# lvc.net
KiCad netlist of a schematic drawn in EAGLE
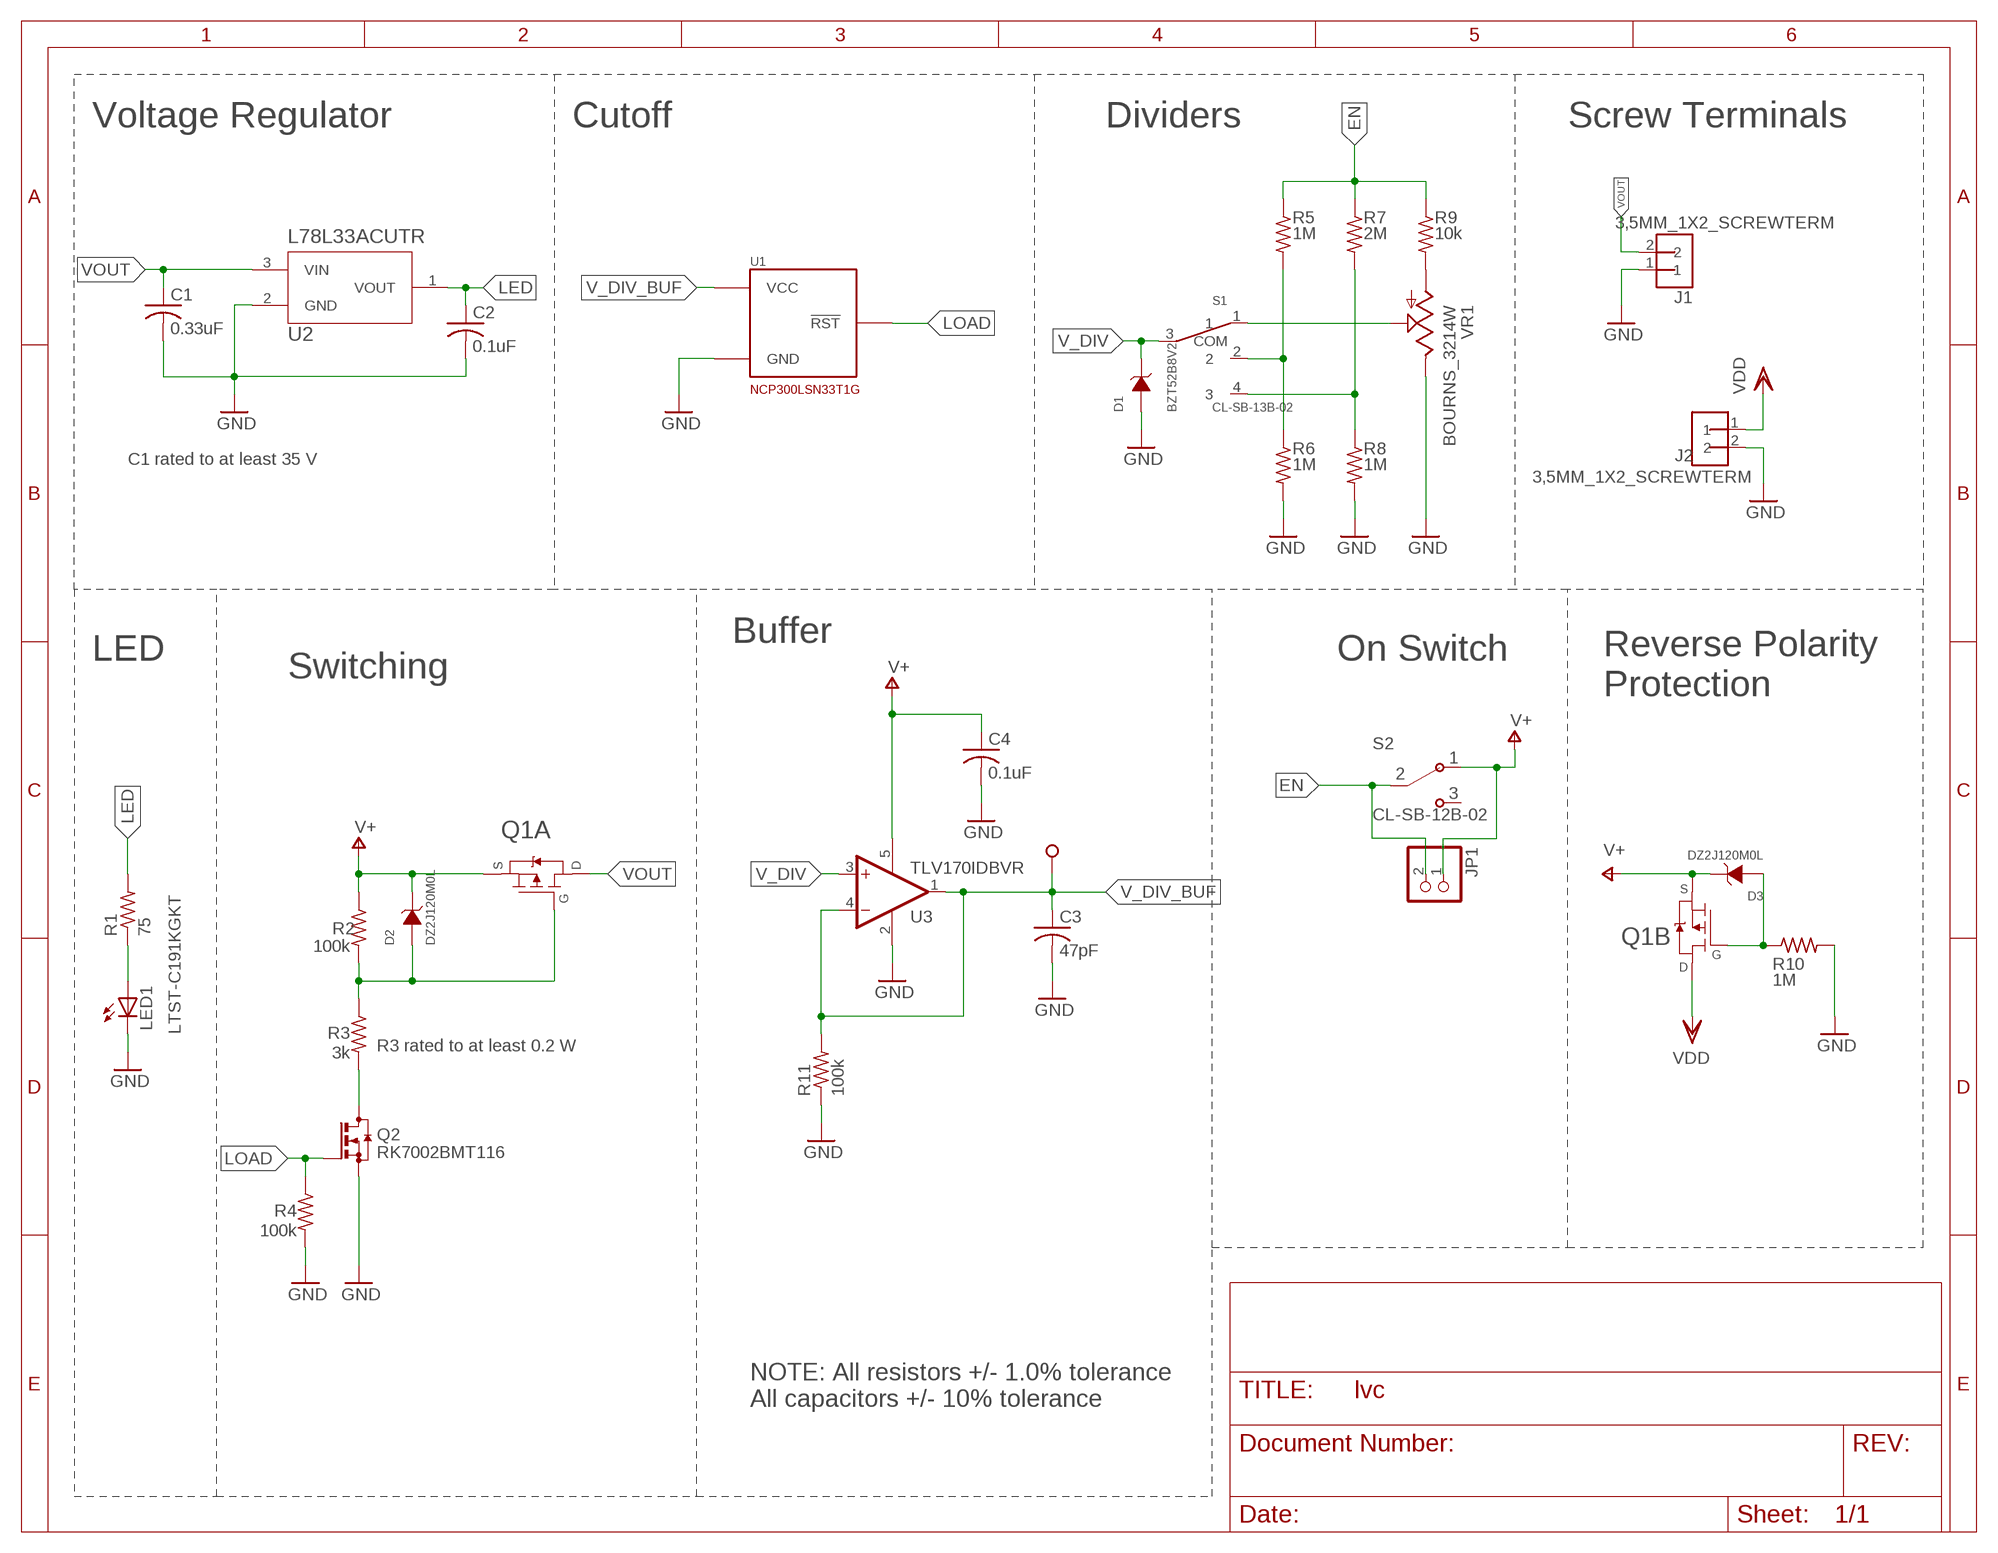
[diagram p0: schematic, sheet 1]

(export (version "E")
  (design (tool "Eeschema 10.0.6"))
  (components
    (comp (ref "C1")
      (value "0.33uF")
      (footprint "eagle-import:C0603")
      (libsource (lib "eagle-import") (part "C-USC0603"))
    )
    (comp (ref "C2")
      (value "0.1uF")
      (footprint "eagle-import:C0603")
      (libsource (lib "eagle-import") (part "C-USC0603"))
    )
    (comp (ref "C3")
      (value "47pF")
      (footprint "eagle-import:C0603")
      (libsource (lib "eagle-import") (part "C-USC0603"))
    )
    (comp (ref "C4")
      (value "0.1uF")
      (footprint "eagle-import:C0603")
      (libsource (lib "eagle-import") (part "C-USC0603"))
    )
    (comp (ref "D1")
      (value "BZT52B8V2")
      (footprint "eagle-import:SOD123")
      (libsource (lib "eagle-import") (part "BZT52B8V2"))
    )
    (comp (ref "D2")
      (value "DZ2J120M0L")
      (footprint "eagle-import:SMINI2-F5-B")
      (libsource (lib "eagle-import") (part "DZ2J120M0L"))
    )
    (comp (ref "D3")
      (value "DZ2J120M0L")
      (footprint "eagle-import:SMINI2-F5-B")
      (libsource (lib "eagle-import") (part "DZ2J120M0L"))
    )
    (comp (ref "J1")
      (value "3,5MM_1X2_SCREWTERM")
      (footprint "eagle-import:3.5MM_1X2")
      (libsource (lib "eagle-import") (part "3,5MM_1X2_SCREWTERM"))
    )
    (comp (ref "J2")
      (value "3,5MM_1X2_SCREWTERM")
      (footprint "eagle-import:3.5MM_1X2")
      (libsource (lib "eagle-import") (part "3,5MM_1X2_SCREWTERM"))
    )
    (comp (ref "JP1")
      (value "PINHD-1X2")
      (footprint "eagle-import:1X02")
      (libsource (lib "eagle-import") (part "PINHD-1X2"))
    )
    (comp (ref "LED1")
      (value "LEDCHIPLED_0603")
      (footprint "eagle-import:CHIPLED_0603")
      (libsource (lib "eagle-import") (part "LEDCHIPLED_0603"))
    )
    (comp (ref "Q1")
      (value "SI7997DP")
      (footprint "eagle-import:POWERPAK-SO-8-DUAL")
      (libsource (lib "eagle-import") (part "SI7997DP"))
    )
    (comp (ref "Q2")
      (value "RK7002BMT116")
      (footprint "eagle-import:SOT23")
      (libsource (lib "eagle-import") (part "RK7002BMT116"))
    )
    (comp (ref "R1")
      (value "75")
      (footprint "eagle-import:R0603")
      (libsource (lib "eagle-import") (part "R-US_R0603"))
    )
    (comp (ref "R2")
      (value "100k")
      (footprint "eagle-import:R0603")
      (libsource (lib "eagle-import") (part "resistor_348_R-US_R0603"))
    )
    (comp (ref "R3")
      (value "3k")
      (footprint "eagle-import:R0603")
      (libsource (lib "eagle-import") (part "resistor_348_R-US_R0603"))
    )
    (comp (ref "R4")
      (value "100k")
      (footprint "eagle-import:R0603")
      (libsource (lib "eagle-import") (part "resistor_348_R-US_R0603"))
    )
    (comp (ref "R5")
      (value "1M")
      (footprint "eagle-import:R0603")
      (libsource (lib "eagle-import") (part "resistor_348_R-US_R0603"))
    )
    (comp (ref "R6")
      (value "1M")
      (footprint "eagle-import:R0603")
      (libsource (lib "eagle-import") (part "resistor_348_R-US_R0603"))
    )
    (comp (ref "R7")
      (value "2M")
      (footprint "eagle-import:R0603")
      (libsource (lib "eagle-import") (part "resistor_348_R-US_R0603"))
    )
    (comp (ref "R8")
      (value "1M")
      (footprint "eagle-import:R0603")
      (libsource (lib "eagle-import") (part "resistor_348_R-US_R0603"))
    )
    (comp (ref "R9")
      (value "10k")
      (footprint "eagle-import:R0603")
      (libsource (lib "eagle-import") (part "resistor_348_R-US_R0603"))
    )
    (comp (ref "R10")
      (value "1M")
      (footprint "eagle-import:R0603")
      (libsource (lib "eagle-import") (part "resistor_348_R-US_R0603"))
    )
    (comp (ref "R11")
      (value "100k")
      (footprint "eagle-import:R0603")
      (libsource (lib "eagle-import") (part "R-US_R0603"))
    )
    (comp (ref "S1")
      (value "CL-SB-13B-02")
      (footprint "eagle-import:CL-SB-13B")
      (libsource (lib "eagle-import") (part "CL-SB-13B-02"))
    )
    (comp (ref "S2")
      (value "CL-SB-12B-02")
      (footprint "eagle-import:CL-SB-12B")
      (libsource (lib "eagle-import") (part "CL-SB-12B-02"))
    )
    (comp (ref "TP2")
      (value "TESTPOINTNOCREAM")
      (footprint "eagle-import:TP_2.5MM_NOCREAM")
      (libsource (lib "eagle-import") (part "TESTPOINTNOCREAM"))
    )
    (comp (ref "U1")
      (value "NCP300LSN33T1G")
      (footprint "eagle-import:SOT23-5")
      (libsource (lib "eagle-import") (part "NCP300LSN33T1G"))
    )
    (comp (ref "U2")
      (value "L78L33ACUTR")
      (footprint "eagle-import:SOT-89")
      (libsource (lib "eagle-import") (part "L78L33ACUTR"))
    )
    (comp (ref "U3")
      (value "TLV170IDBVR")
      (footprint "eagle-import:SOT23-DBV")
      (libsource (lib "eagle-import") (part "TLV170IDBVR"))
    )
    (comp (ref "VR1")
      (value "BOURNS_3214W")
      (footprint "eagle-import:J-LEAD_TOP_ADJ")
      (libsource (lib "eagle-import") (part "BOURNS_3214W"))
    )
  )
  (nets
    (net (code "1") (name "EN") (class "Default")
      (node (ref "JP1") (pin "2") (pinfunction "2_2") (pintype "passive"))
      (node (ref "R5") (pin "1") (pinfunction "1_1") (pintype "passive"))
      (node (ref "R7") (pin "1") (pinfunction "1_1") (pintype "passive"))
      (node (ref "R9") (pin "1") (pinfunction "1_1") (pintype "passive"))
      (node (ref "S2") (pin "1") (pinfunction "P$1_1") (pintype "bidirectional"))
    )
    (net (code "2") (name "GND") (class "Default")
      (node (ref "C1") (pin "2") (pinfunction "2_2") (pintype "passive"))
      (node (ref "C2") (pin "2") (pinfunction "2_2") (pintype "passive"))
      (node (ref "C3") (pin "2") (pinfunction "2_2") (pintype "passive"))
      (node (ref "C4") (pin "2") (pinfunction "2_2") (pintype "passive"))
      (node (ref "D1") (pin "A") (pinfunction "A_A") (pintype "bidirectional"))
      (node (ref "J1") (pin "1") (pinfunction "1_1") (pintype "bidirectional"))
      (node (ref "J2") (pin "2") (pinfunction "2_2") (pintype "bidirectional"))
      (node (ref "LED1") (pin "C") (pinfunction "C_C") (pintype "passive"))
      (node (ref "Q2") (pin "2") (pinfunction "S_2") (pintype "passive"))
      (node (ref "R10") (pin "2") (pinfunction "2_2") (pintype "passive"))
      (node (ref "R11") (pin "1") (pinfunction "1_1") (pintype "passive"))
      (node (ref "R4") (pin "2") (pinfunction "2_2") (pintype "passive"))
      (node (ref "R6") (pin "2") (pinfunction "2_2") (pintype "passive"))
      (node (ref "R8") (pin "2") (pinfunction "2_2") (pintype "passive"))
      (node (ref "U1") (pin "3") (pinfunction "GND_3") (pintype "power_in"))
      (node (ref "U2") (pin "2") (pinfunction "GND_2") (pintype "passive"))
      (node (ref "U3") (pin "2") (pinfunction "V-_2") (pintype "power_in"))
      (node (ref "VR1") (pin "3") (pinfunction "E_3") (pintype "passive"))
    )
    (net (code "3") (name "LED") (class "Default")
      (node (ref "C2") (pin "1") (pinfunction "1_1") (pintype "passive"))
      (node (ref "R1") (pin "2") (pinfunction "2_2") (pintype "passive"))
      (node (ref "U2") (pin "1") (pinfunction "VOUT_1") (pintype "output"))
    )
    (net (code "4") (name "LOAD") (class "Default")
      (node (ref "Q2") (pin "1") (pinfunction "G_1") (pintype "passive"))
      (node (ref "R4") (pin "1") (pinfunction "1_1") (pintype "passive"))
      (node (ref "U1") (pin "1") (pinfunction "~{RST}_1") (pintype "bidirectional"))
    )
    (net (code "5") (name "Net-(LED1-PadA)") (class "Default")
      (node (ref "LED1") (pin "A") (pinfunction "A_A") (pintype "passive"))
      (node (ref "R1") (pin "1") (pinfunction "1_1") (pintype "passive"))
    )
    (net (code "6") (name "Net-(Q1A-G)") (class "Default")
      (node (ref "D2") (pin "A") (pinfunction "A_A") (pintype "passive"))
      (node (ref "Q1") (pin "4") (pinfunction "G_4") (pintype "bidirectional"))
      (node (ref "R2") (pin "2") (pinfunction "2_2") (pintype "passive"))
      (node (ref "R3") (pin "1") (pinfunction "1_1") (pintype "passive"))
    )
    (net (code "7") (name "Net-(Q1B-G)") (class "Default")
      (node (ref "D3") (pin "A") (pinfunction "A_A") (pintype "passive"))
      (node (ref "Q1") (pin "2") (pinfunction "G_2") (pintype "bidirectional"))
      (node (ref "R10") (pin "1") (pinfunction "1_1") (pintype "passive"))
    )
    (net (code "8") (name "Net-(Q2-D)") (class "Default")
      (node (ref "Q2") (pin "3") (pinfunction "D_3") (pintype "passive"))
      (node (ref "R3") (pin "2") (pinfunction "2_2") (pintype "passive"))
    )
    (net (code "9") (name "Net-(R5-Pad2)") (class "Default")
      (node (ref "R5") (pin "2") (pinfunction "2_2") (pintype "passive"))
      (node (ref "R6") (pin "1") (pinfunction "1_1") (pintype "passive"))
      (node (ref "S1") (pin "2") (pinfunction "2_2") (pintype "bidirectional"))
    )
    (net (code "10") (name "Net-(S1-3)") (class "Default")
      (node (ref "R7") (pin "2") (pinfunction "2_2") (pintype "passive"))
      (node (ref "R8") (pin "1") (pinfunction "1_1") (pintype "passive"))
      (node (ref "S1") (pin "4") (pinfunction "3_4") (pintype "bidirectional"))
    )
    (net (code "11") (name "Net-(VR1-A)") (class "Default")
      (node (ref "R9") (pin "2") (pinfunction "2_2") (pintype "passive"))
      (node (ref "VR1") (pin "1") (pinfunction "A_1") (pintype "passive"))
    )
    (net (code "12") (name "Net-(VR1-S)") (class "Default")
      (node (ref "S1") (pin "1") (pinfunction "1_1") (pintype "bidirectional"))
      (node (ref "VR1") (pin "2") (pinfunction "S_2") (pintype "passive"))
    )
    (net (code "13") (name "V+") (class "Default")
      (node (ref "C4") (pin "1") (pinfunction "1_1") (pintype "passive"))
      (node (ref "D2") (pin "C") (pinfunction "C_C") (pintype "passive"))
      (node (ref "D3") (pin "C") (pinfunction "C_C") (pintype "passive"))
      (node (ref "JP1") (pin "1") (pinfunction "1_1") (pintype "passive"))
      (node (ref "Q1") (pin "1") (pinfunction "S_1") (pintype "bidirectional"))
      (node (ref "Q1") (pin "3") (pinfunction "S_3") (pintype "bidirectional"))
      (node (ref "R2") (pin "1") (pinfunction "1_1") (pintype "passive"))
      (node (ref "S2") (pin "2") (pinfunction "P$2_2") (pintype "bidirectional"))
      (node (ref "U3") (pin "5") (pinfunction "V+_5") (pintype "power_in"))
    )
    (net (code "14") (name "VDD") (class "Default")
      (node (ref "J2") (pin "1") (pinfunction "1_1") (pintype "bidirectional"))
      (node (ref "Q1") (pin "7") (pinfunction "D_7") (pintype "bidirectional"))
      (node (ref "Q1") (pin "8") (pinfunction "D_8") (pintype "bidirectional"))
      (node (ref "Q1") (pin "8L") (pinfunction "D_8L") (pintype "bidirectional"))
    )
    (net (code "15") (name "VOUT") (class "Default")
      (node (ref "C1") (pin "1") (pinfunction "1_1") (pintype "passive"))
      (node (ref "J1") (pin "2") (pinfunction "2_2") (pintype "bidirectional"))
      (node (ref "Q1") (pin "5") (pinfunction "D_5") (pintype "bidirectional"))
      (node (ref "Q1") (pin "5L") (pinfunction "D_5L") (pintype "bidirectional"))
      (node (ref "Q1") (pin "6") (pinfunction "D_6") (pintype "bidirectional"))
      (node (ref "U2") (pin "3") (pinfunction "VIN_3") (pintype "input"))
    )
    (net (code "16") (name "V_DIV") (class "Default")
      (node (ref "D1") (pin "C") (pinfunction "C_C") (pintype "bidirectional"))
      (node (ref "S1") (pin "3") (pinfunction "COM_3") (pintype "bidirectional"))
      (node (ref "U3") (pin "3") (pinfunction "+IN_3") (pintype "input"))
    )
    (net (code "17") (name "V_DIV_BUF") (class "Default")
      (node (ref "C3") (pin "1") (pinfunction "1_1") (pintype "passive"))
      (node (ref "R11") (pin "2") (pinfunction "2_2") (pintype "passive"))
      (node (ref "TP2") (pin "P$1") (pinfunction "P$1_P$1") (pintype "bidirectional"))
      (node (ref "U1") (pin "2") (pinfunction "VCC_2") (pintype "power_in"))
      (node (ref "U3") (pin "1") (pinfunction "OUT_1") (pintype "output"))
      (node (ref "U3") (pin "4") (pinfunction "-IN_4") (pintype "input"))
    )
    (net (code "18") (name "unconnected-(S2-P$3-Pad3)") (class "Default")
      (node (ref "S2") (pin "3") (pinfunction "P$3_3") (pintype "bidirectional"))
    )
  )
)
